# smd_version_01.net
KiCad netlist of a schematic drawn in EAGLE
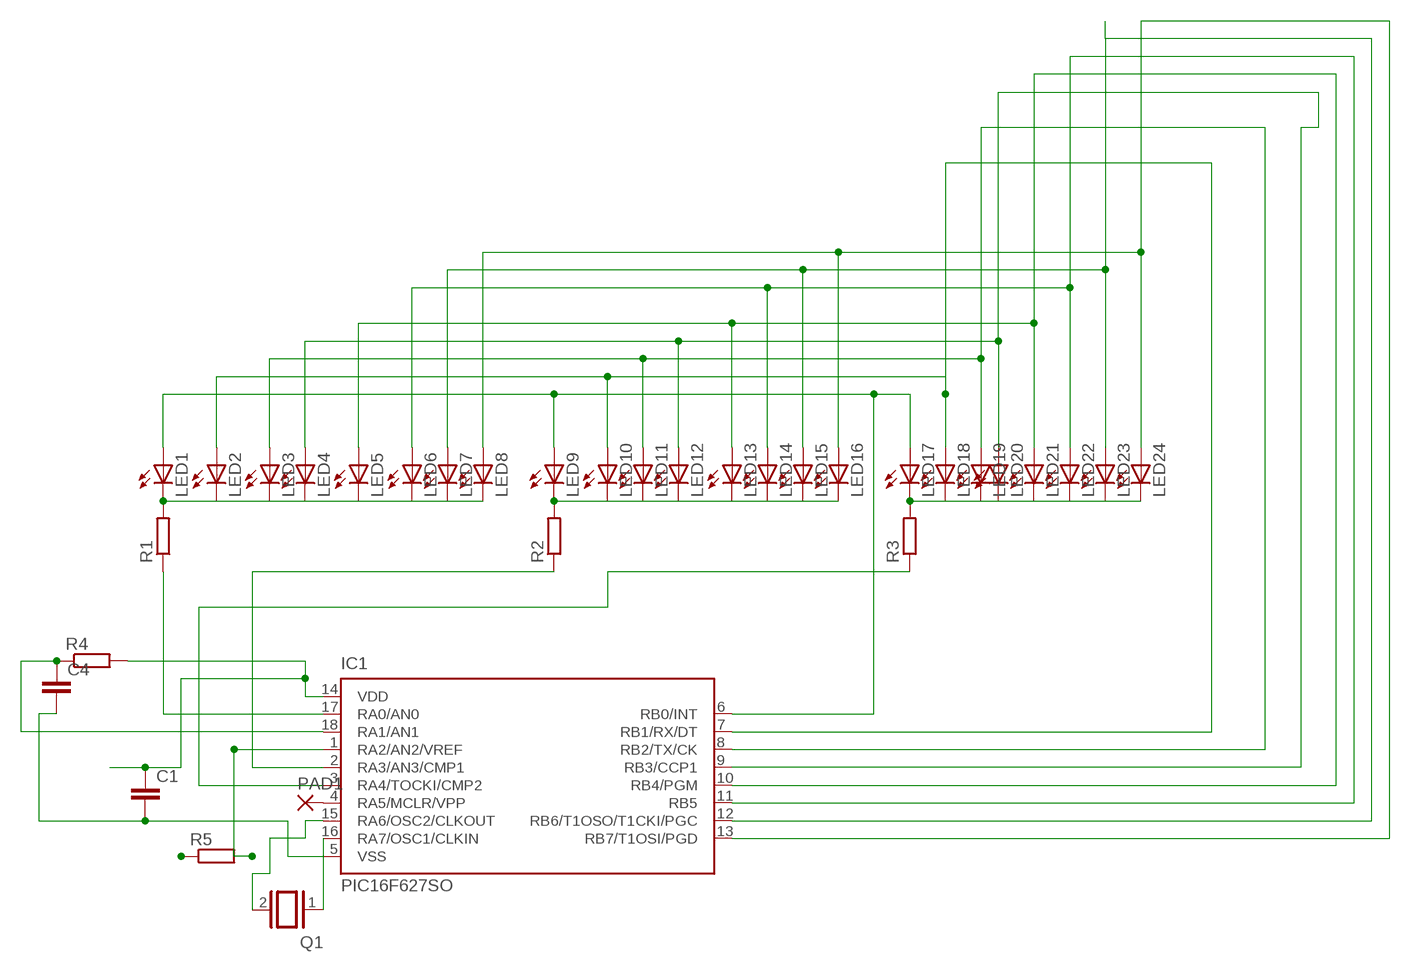
[diagram p0: schematic, sheet 1]

(export (version "E")
  (design (tool "Eeschema 10.0.6"))
  (components
    (comp (ref "C1")
      (value "C-EUC1825")
      (footprint "eagle-import:C1825")
      (libsource (lib "eagle-import") (part "C-EUC1825"))
    )
    (comp (ref "C4")
      (value "C-EUC0805")
      (footprint "eagle-import:C0805")
      (libsource (lib "eagle-import") (part "C-EUC0805"))
    )
    (comp (ref "IC1")
      (value "PIC16F627SO")
      (footprint "eagle-import:SO-18W")
      (libsource (lib "eagle-import") (part "PIC16F62SO7"))
    )
    (comp (ref "LED1")
      (value "LEDSMT1206")
      (footprint "eagle-import:1206")
      (libsource (lib "eagle-import") (part "LEDSMT1206"))
    )
    (comp (ref "LED2")
      (value "LEDSMT1206")
      (footprint "eagle-import:1206")
      (libsource (lib "eagle-import") (part "LEDSMT1206"))
    )
    (comp (ref "LED3")
      (value "LEDSMT1206")
      (footprint "eagle-import:1206")
      (libsource (lib "eagle-import") (part "LEDSMT1206"))
    )
    (comp (ref "LED4")
      (value "LEDSMT1206")
      (footprint "eagle-import:1206")
      (libsource (lib "eagle-import") (part "LEDSMT1206"))
    )
    (comp (ref "LED5")
      (value "LEDSMT1206")
      (footprint "eagle-import:1206")
      (libsource (lib "eagle-import") (part "LEDSMT1206"))
    )
    (comp (ref "LED6")
      (value "LEDSMT1206")
      (footprint "eagle-import:1206")
      (libsource (lib "eagle-import") (part "LEDSMT1206"))
    )
    (comp (ref "LED7")
      (value "LEDSMT1206")
      (footprint "eagle-import:1206")
      (libsource (lib "eagle-import") (part "LEDSMT1206"))
    )
    (comp (ref "LED8")
      (value "LEDSMT1206")
      (footprint "eagle-import:1206")
      (libsource (lib "eagle-import") (part "LEDSMT1206"))
    )
    (comp (ref "LED9")
      (value "LEDSMT1206")
      (footprint "eagle-import:1206")
      (libsource (lib "eagle-import") (part "LEDSMT1206"))
    )
    (comp (ref "LED10")
      (value "LEDSMT1206")
      (footprint "eagle-import:1206")
      (libsource (lib "eagle-import") (part "LEDSMT1206"))
    )
    (comp (ref "LED11")
      (value "LEDSMT1206")
      (footprint "eagle-import:1206")
      (libsource (lib "eagle-import") (part "LEDSMT1206"))
    )
    (comp (ref "LED12")
      (value "LEDSMT1206")
      (footprint "eagle-import:1206")
      (libsource (lib "eagle-import") (part "LEDSMT1206"))
    )
    (comp (ref "LED13")
      (value "LEDSMT1206")
      (footprint "eagle-import:1206")
      (libsource (lib "eagle-import") (part "LEDSMT1206"))
    )
    (comp (ref "LED14")
      (value "LEDSMT1206")
      (footprint "eagle-import:1206")
      (libsource (lib "eagle-import") (part "LEDSMT1206"))
    )
    (comp (ref "LED15")
      (value "LEDSMT1206")
      (footprint "eagle-import:1206")
      (libsource (lib "eagle-import") (part "LEDSMT1206"))
    )
    (comp (ref "LED16")
      (value "LEDSMT1206")
      (footprint "eagle-import:1206")
      (libsource (lib "eagle-import") (part "LEDSMT1206"))
    )
    (comp (ref "LED17")
      (value "LEDSMT1206")
      (footprint "eagle-import:1206")
      (libsource (lib "eagle-import") (part "LEDSMT1206"))
    )
    (comp (ref "LED18")
      (value "LEDSMT1206")
      (footprint "eagle-import:1206")
      (libsource (lib "eagle-import") (part "LEDSMT1206"))
    )
    (comp (ref "LED19")
      (value "LEDSMT1206")
      (footprint "eagle-import:1206")
      (libsource (lib "eagle-import") (part "LEDSMT1206"))
    )
    (comp (ref "LED20")
      (value "LEDSMT1206")
      (footprint "eagle-import:1206")
      (libsource (lib "eagle-import") (part "LEDSMT1206"))
    )
    (comp (ref "LED21")
      (value "LEDSMT1206")
      (footprint "eagle-import:1206")
      (libsource (lib "eagle-import") (part "LEDSMT1206"))
    )
    (comp (ref "LED22")
      (value "LEDSMT1206")
      (footprint "eagle-import:1206")
      (libsource (lib "eagle-import") (part "LEDSMT1206"))
    )
    (comp (ref "LED23")
      (value "LEDSMT1206")
      (footprint "eagle-import:1206")
      (libsource (lib "eagle-import") (part "LEDSMT1206"))
    )
    (comp (ref "LED24")
      (value "LEDSMT1206")
      (footprint "eagle-import:1206")
      (libsource (lib "eagle-import") (part "LEDSMT1206"))
    )
    (comp (ref "PAD1")
      (value "SMD2")
      (footprint "eagle-import:SMD1,27-2,54")
      (libsource (lib "eagle-import") (part "SMD2"))
    )
    (comp (ref "Q1")
      (value "XTAL/S")
      (footprint "eagle-import:QS")
      (libsource (lib "eagle-import") (part "XTAL/S"))
    )
    (comp (ref "R1")
      (value "R-EU_0207/15")
      (footprint "eagle-import:0207_15")
      (libsource (lib "eagle-import") (part "R-EU_0207/15"))
    )
    (comp (ref "R2")
      (value "R-EU_0207/15")
      (footprint "eagle-import:0207_15")
      (libsource (lib "eagle-import") (part "R-EU_0207/15"))
    )
    (comp (ref "R3")
      (value "R-EU_0207/15")
      (footprint "eagle-import:0207_15")
      (libsource (lib "eagle-import") (part "R-EU_0207/15"))
    )
    (comp (ref "R4")
      (value "R-EU_M1406")
      (footprint "eagle-import:M1406")
      (libsource (lib "eagle-import") (part "resistor_R-EU_M1406"))
    )
    (comp (ref "R5")
      (value "R-EU_0207/12")
      (footprint "eagle-import:0207_12")
      (libsource (lib "eagle-import") (part "R-EU_0207/12"))
    )
  )
  (nets
    (net (code "1") (name "Net-(IC1-RA0{slash}AN0)") (class "Default")
      (node (ref "IC1") (pin "17") (pinfunction "RA0/AN0_17") (pintype "bidirectional"))
      (node (ref "R1") (pin "1") (pinfunction "1_1") (pintype "passive"))
    )
    (net (code "2") (name "Net-(IC1-RA1{slash}AN1)") (class "Default")
      (node (ref "C4") (pin "1") (pinfunction "1_1") (pintype "passive"))
      (node (ref "IC1") (pin "18") (pinfunction "RA1/AN1_18") (pintype "bidirectional"))
      (node (ref "R4") (pin "1") (pinfunction "1_1") (pintype "passive"))
    )
    (net (code "3") (name "Net-(IC1-RA2{slash}AN2{slash}VREF)") (class "Default")
      (node (ref "IC1") (pin "1") (pinfunction "RA2/AN2/VREF_1") (pintype "bidirectional"))
      (node (ref "R5") (pin "2") (pinfunction "2_2") (pintype "passive"))
    )
    (net (code "4") (name "Net-(IC1-RA3{slash}AN3{slash}CMP1)") (class "Default")
      (node (ref "IC1") (pin "2") (pinfunction "RA3/AN3/CMP1_2") (pintype "bidirectional"))
      (node (ref "R2") (pin "1") (pinfunction "1_1") (pintype "passive"))
    )
    (net (code "5") (name "Net-(IC1-RA4{slash}TOCKI{slash}CMP2)") (class "Default")
      (node (ref "IC1") (pin "3") (pinfunction "RA4/TOCKI/CMP2_3") (pintype "bidirectional"))
      (node (ref "R3") (pin "1") (pinfunction "1_1") (pintype "passive"))
    )
    (net (code "6") (name "Net-(IC1-RA5{slash}MCLR{slash}VPP)") (class "Default")
      (node (ref "IC1") (pin "4") (pinfunction "RA5/MCLR/VPP_4") (pintype "bidirectional"))
      (node (ref "PAD1") (pin "1") (pinfunction "P_1") (pintype "passive"))
    )
    (net (code "7") (name "Net-(IC1-RA6{slash}OSC2{slash}CLKOUT)") (class "Default")
      (node (ref "IC1") (pin "15") (pinfunction "RA6/OSC2/CLKOUT_15") (pintype "bidirectional"))
      (node (ref "Q1") (pin "2") (pinfunction "2_2") (pintype "passive"))
    )
    (net (code "8") (name "Net-(IC1-RA7{slash}OSC1{slash}CLKIN)") (class "Default")
      (node (ref "IC1") (pin "16") (pinfunction "RA7/OSC1/CLKIN_16") (pintype "bidirectional"))
      (node (ref "Q1") (pin "1") (pinfunction "1_1") (pintype "passive"))
    )
    (net (code "9") (name "Net-(IC1-RB0{slash}INT)") (class "Default")
      (node (ref "IC1") (pin "6") (pinfunction "RB0/INT_6") (pintype "bidirectional"))
      (node (ref "LED1") (pin "A") (pinfunction "A_A") (pintype "passive"))
      (node (ref "LED17") (pin "A") (pinfunction "A_A") (pintype "passive"))
      (node (ref "LED9") (pin "A") (pinfunction "A_A") (pintype "passive"))
    )
    (net (code "10") (name "Net-(IC1-RB1{slash}RX{slash}DT)") (class "Default")
      (node (ref "IC1") (pin "7") (pinfunction "RB1/RX/DT_7") (pintype "bidirectional"))
      (node (ref "LED10") (pin "A") (pinfunction "A_A") (pintype "passive"))
      (node (ref "LED18") (pin "A") (pinfunction "A_A") (pintype "passive"))
      (node (ref "LED2") (pin "A") (pinfunction "A_A") (pintype "passive"))
    )
    (net (code "11") (name "Net-(IC1-RB2{slash}TX{slash}CK)") (class "Default")
      (node (ref "IC1") (pin "8") (pinfunction "RB2/TX/CK_8") (pintype "bidirectional"))
      (node (ref "LED11") (pin "A") (pinfunction "A_A") (pintype "passive"))
      (node (ref "LED19") (pin "A") (pinfunction "A_A") (pintype "passive"))
      (node (ref "LED3") (pin "A") (pinfunction "A_A") (pintype "passive"))
    )
    (net (code "12") (name "Net-(IC1-RB3{slash}CCP1)") (class "Default")
      (node (ref "IC1") (pin "9") (pinfunction "RB3/CCP1_9") (pintype "bidirectional"))
      (node (ref "LED12") (pin "A") (pinfunction "A_A") (pintype "passive"))
      (node (ref "LED20") (pin "A") (pinfunction "A_A") (pintype "passive"))
      (node (ref "LED4") (pin "A") (pinfunction "A_A") (pintype "passive"))
    )
    (net (code "13") (name "Net-(IC1-RB4{slash}PGM)") (class "Default")
      (node (ref "IC1") (pin "10") (pinfunction "RB4/PGM_10") (pintype "bidirectional"))
      (node (ref "LED13") (pin "A") (pinfunction "A_A") (pintype "passive"))
      (node (ref "LED21") (pin "A") (pinfunction "A_A") (pintype "passive"))
      (node (ref "LED5") (pin "A") (pinfunction "A_A") (pintype "passive"))
    )
    (net (code "14") (name "Net-(IC1-RB5)") (class "Default")
      (node (ref "IC1") (pin "11") (pinfunction "RB5_11") (pintype "bidirectional"))
      (node (ref "LED14") (pin "A") (pinfunction "A_A") (pintype "passive"))
      (node (ref "LED22") (pin "A") (pinfunction "A_A") (pintype "passive"))
      (node (ref "LED6") (pin "A") (pinfunction "A_A") (pintype "passive"))
    )
    (net (code "15") (name "Net-(IC1-RB6{slash}T1OSO{slash}T1CKI{slash}PGC)") (class "Default")
      (node (ref "IC1") (pin "12") (pinfunction "RB6/T1OSO/T1CKI/PGC_12") (pintype "bidirectional"))
      (node (ref "LED15") (pin "A") (pinfunction "A_A") (pintype "passive"))
      (node (ref "LED23") (pin "A") (pinfunction "A_A") (pintype "passive"))
      (node (ref "LED7") (pin "A") (pinfunction "A_A") (pintype "passive"))
    )
    (net (code "16") (name "Net-(IC1-RB7{slash}T1OSI{slash}PGD)") (class "Default")
      (node (ref "IC1") (pin "13") (pinfunction "RB7/T1OSI/PGD_13") (pintype "bidirectional"))
      (node (ref "LED16") (pin "A") (pinfunction "A_A") (pintype "passive"))
      (node (ref "LED24") (pin "A") (pinfunction "A_A") (pintype "passive"))
      (node (ref "LED8") (pin "A") (pinfunction "A_A") (pintype "passive"))
    )
    (net (code "17") (name "Net-(IC1-VDD)") (class "Default")
      (node (ref "C1") (pin "1") (pinfunction "1_1") (pintype "passive"))
      (node (ref "IC1") (pin "14") (pinfunction "VDD_14") (pintype "power_in"))
      (node (ref "R4") (pin "2") (pinfunction "2_2") (pintype "passive"))
    )
    (net (code "18") (name "Net-(IC1-VSS)") (class "Default")
      (node (ref "C1") (pin "2") (pinfunction "2_2") (pintype "passive"))
      (node (ref "C4") (pin "2") (pinfunction "2_2") (pintype "passive"))
      (node (ref "IC1") (pin "5") (pinfunction "VSS_5") (pintype "power_in"))
    )
    (net (code "19") (name "Net-(LED1-PadC)") (class "Default")
      (node (ref "LED1") (pin "C") (pinfunction "C_C") (pintype "passive"))
      (node (ref "LED2") (pin "C") (pinfunction "C_C") (pintype "passive"))
      (node (ref "LED3") (pin "C") (pinfunction "C_C") (pintype "passive"))
      (node (ref "LED4") (pin "C") (pinfunction "C_C") (pintype "passive"))
      (node (ref "LED5") (pin "C") (pinfunction "C_C") (pintype "passive"))
      (node (ref "LED6") (pin "C") (pinfunction "C_C") (pintype "passive"))
      (node (ref "LED7") (pin "C") (pinfunction "C_C") (pintype "passive"))
      (node (ref "LED8") (pin "C") (pinfunction "C_C") (pintype "passive"))
      (node (ref "R1") (pin "2") (pinfunction "2_2") (pintype "passive"))
    )
    (net (code "20") (name "Net-(LED10-PadC)") (class "Default")
      (node (ref "LED10") (pin "C") (pinfunction "C_C") (pintype "passive"))
      (node (ref "LED11") (pin "C") (pinfunction "C_C") (pintype "passive"))
      (node (ref "LED12") (pin "C") (pinfunction "C_C") (pintype "passive"))
      (node (ref "LED13") (pin "C") (pinfunction "C_C") (pintype "passive"))
      (node (ref "LED14") (pin "C") (pinfunction "C_C") (pintype "passive"))
      (node (ref "LED15") (pin "C") (pinfunction "C_C") (pintype "passive"))
      (node (ref "LED16") (pin "C") (pinfunction "C_C") (pintype "passive"))
      (node (ref "LED9") (pin "C") (pinfunction "C_C") (pintype "passive"))
      (node (ref "R2") (pin "2") (pinfunction "2_2") (pintype "passive"))
    )
    (net (code "21") (name "Net-(LED17-PadC)") (class "Default")
      (node (ref "LED17") (pin "C") (pinfunction "C_C") (pintype "passive"))
      (node (ref "LED18") (pin "C") (pinfunction "C_C") (pintype "passive"))
      (node (ref "LED19") (pin "C") (pinfunction "C_C") (pintype "passive"))
      (node (ref "LED20") (pin "C") (pinfunction "C_C") (pintype "passive"))
      (node (ref "LED21") (pin "C") (pinfunction "C_C") (pintype "passive"))
      (node (ref "LED22") (pin "C") (pinfunction "C_C") (pintype "passive"))
      (node (ref "LED23") (pin "C") (pinfunction "C_C") (pintype "passive"))
      (node (ref "LED24") (pin "C") (pinfunction "C_C") (pintype "passive"))
      (node (ref "R3") (pin "2") (pinfunction "2_2") (pintype "passive"))
    )
    (net (code "22") (name "unconnected-(R5-Pad1)") (class "Default")
      (node (ref "R5") (pin "1") (pinfunction "1_1") (pintype "passive"))
    )
  )
)
